# IF_transformer.net
KiCad netlist of a schematic drawn in Altium Designer
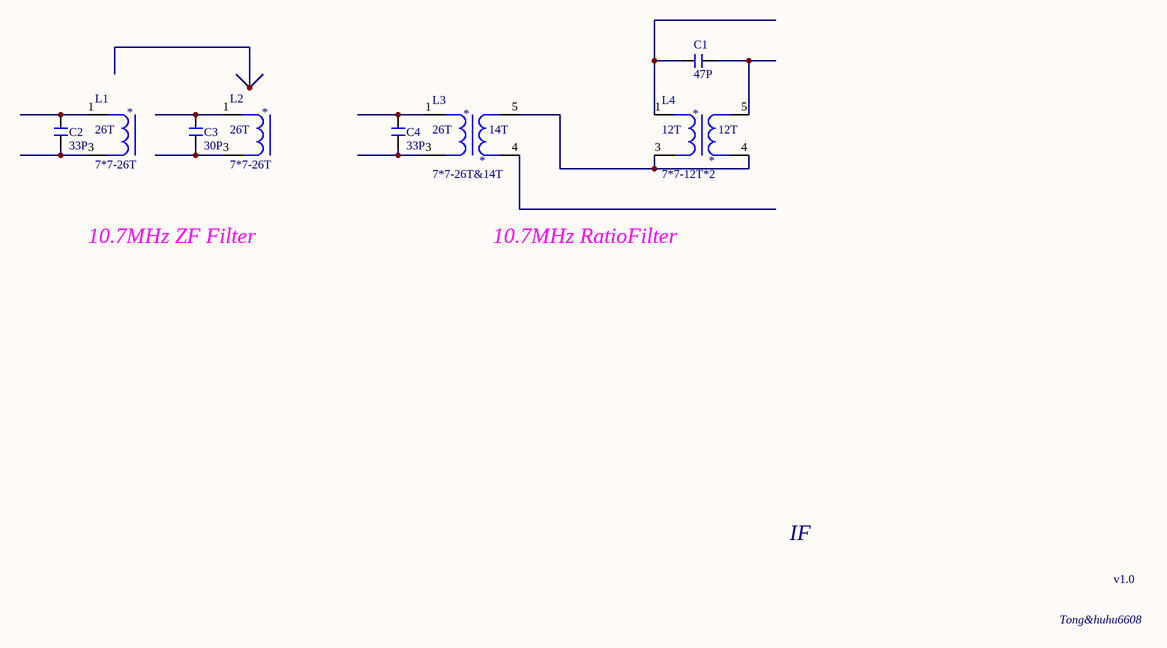
[diagram p0: IF_transformer.SchDoc]

(export (version "E")
  (design (tool "Eeschema 10.0.6"))
  (components
    (comp (ref "C1")
      (value "47P")
      (footprint "C 1206")
      (description "瓷片电容-贴片")
      (libsource (lib "ALl") (part "Cap-CER-SMD"))
    )
    (comp (ref "C2")
      (value "33P")
      (footprint "C 1206")
      (description "瓷片电容-贴片")
      (libsource (lib "ALl") (part "Cap-CER-SMD"))
    )
    (comp (ref "C3")
      (value "30P")
      (footprint "C 1206")
      (description "瓷片电容-贴片")
      (libsource (lib "ALl") (part "Cap-CER-SMD"))
    )
    (comp (ref "C4")
      (value "33P")
      (footprint "C 1206")
      (description "瓷片电容-贴片")
      (libsource (lib "ALl") (part "Cap-CER-SMD"))
    )
    (comp (ref "L1") (value "7*7-26T") (footprint "adj_L_77") (libsource (lib "ALl") (part "7*7-26T")))
    (comp (ref "L2") (value "7*7-26T") (footprint "adj_L_77") (libsource (lib "ALl") (part "7*7-26T")))
    (comp (ref "L3")
      (value "7*7-26T&14T")
      (footprint "adj_L_77")
      (libsource (lib "ALl") (part "7*7-26T&14T"))
    )
    (comp (ref "L4") (value "7*7-12T*2") (footprint "adj_L_77") (libsource (lib "ALl") (part "7*7-12T*2")))
  )
  (nets
    (net (code "1") (name "Net-(C1-Pad1)") (class "Default")
      (node (ref "C1") (pin "1") (pinfunction "1_1") (pintype "passive"))
      (node (ref "L4") (pin "1") (pinfunction "1_1") (pintype "passive"))
    )
    (net (code "2") (name "Net-(C1-Pad2)") (class "Default")
      (node (ref "C1") (pin "2") (pinfunction "2_2") (pintype "passive"))
      (node (ref "L4") (pin "5") (pinfunction "5_5") (pintype "passive"))
    )
    (net (code "3") (name "Net-(C2-Pad1)") (class "Default")
      (node (ref "C2") (pin "1") (pinfunction "1_1") (pintype "passive"))
      (node (ref "L1") (pin "1") (pinfunction "1_1") (pintype "passive"))
    )
    (net (code "4") (name "Net-(C2-Pad2)") (class "Default")
      (node (ref "C2") (pin "2") (pinfunction "2_2") (pintype "passive"))
      (node (ref "L1") (pin "3") (pinfunction "3_3") (pintype "passive"))
    )
    (net (code "5") (name "Net-(C3-Pad1)") (class "Default")
      (node (ref "C3") (pin "1") (pinfunction "1_1") (pintype "passive"))
      (node (ref "L2") (pin "1") (pinfunction "1_1") (pintype "passive"))
    )
    (net (code "6") (name "Net-(C3-Pad2)") (class "Default")
      (node (ref "C3") (pin "2") (pinfunction "2_2") (pintype "passive"))
      (node (ref "L2") (pin "3") (pinfunction "3_3") (pintype "passive"))
    )
    (net (code "7") (name "Net-(C4-Pad1)") (class "Default")
      (node (ref "C4") (pin "1") (pinfunction "1_1") (pintype "passive"))
      (node (ref "L3") (pin "1") (pinfunction "1_1") (pintype "passive"))
    )
    (net (code "8") (name "Net-(C4-Pad2)") (class "Default")
      (node (ref "C4") (pin "2") (pinfunction "2_2") (pintype "passive"))
      (node (ref "L3") (pin "3") (pinfunction "3_3") (pintype "passive"))
    )
    (net (code "9") (name "Net-(L3-Pad5)") (class "Default")
      (node (ref "L3") (pin "5") (pinfunction "5_5") (pintype "passive"))
      (node (ref "L4") (pin "3") (pinfunction "3_3") (pintype "passive"))
      (node (ref "L4") (pin "4") (pinfunction "4_4") (pintype "passive"))
    )
    (net (code "10") (name "unconnected-(L3-Pad4)") (class "Default")
      (node (ref "L3") (pin "4") (pinfunction "4_4") (pintype "passive"))
    )
  )
)
